# standalone-wifi-module-v1.net
KiCad netlist of a schematic drawn in EAGLE
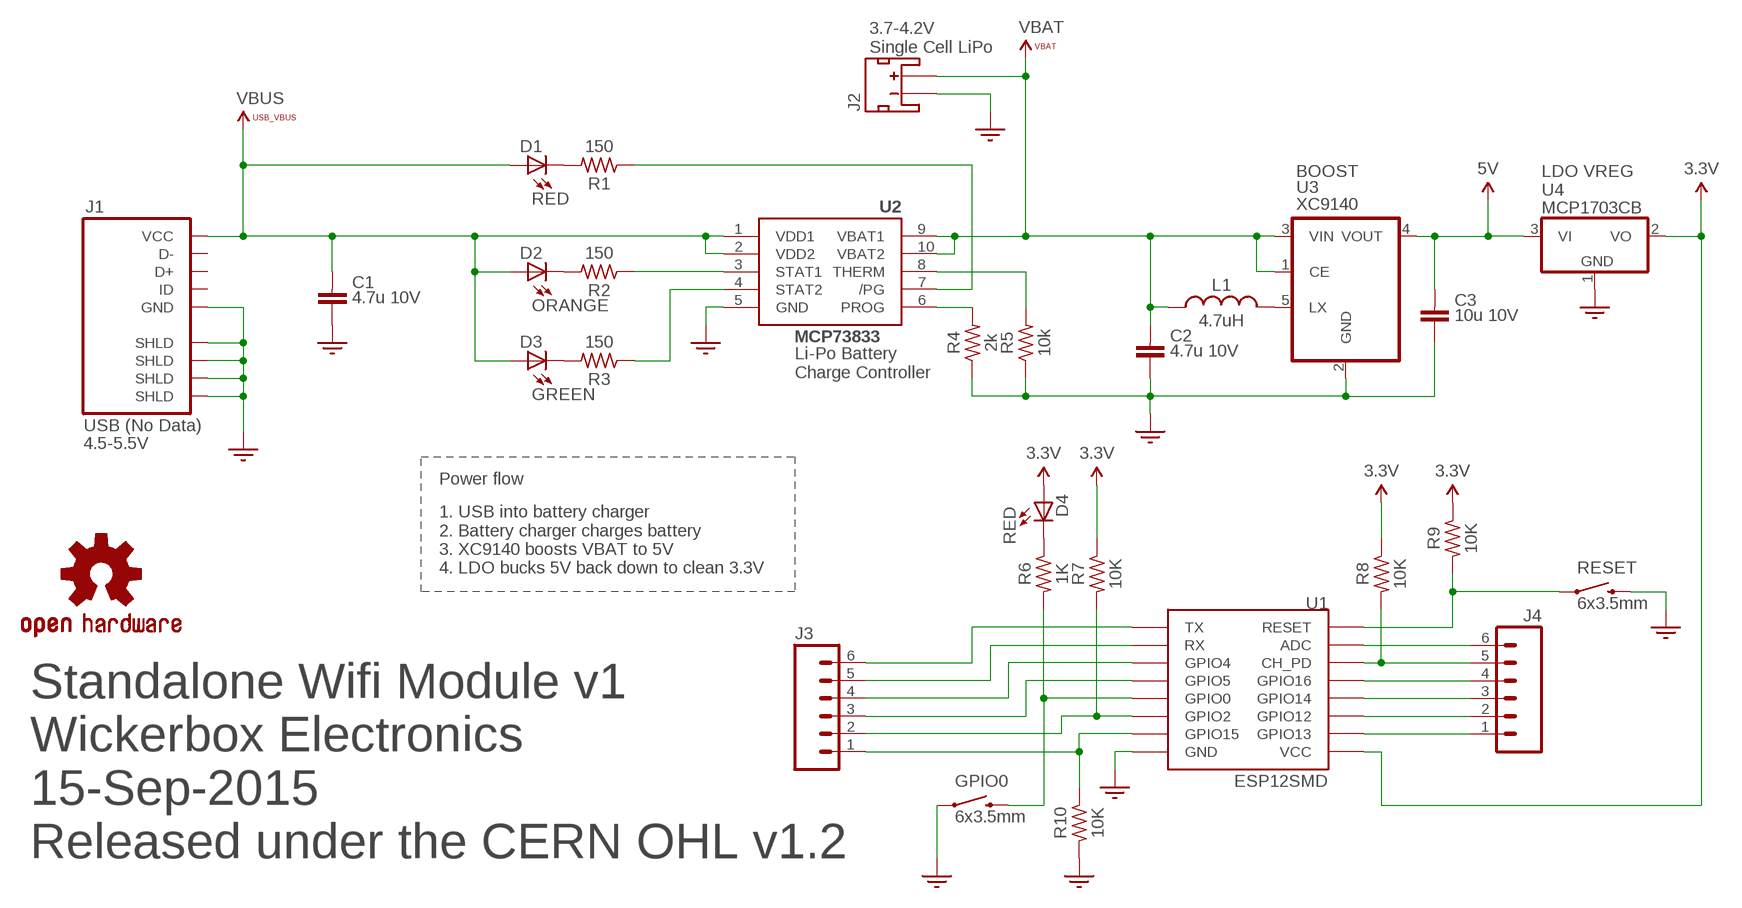
[diagram p0: schematic, sheet 1]

(export (version "E")
  (design (tool "Eeschema 10.0.6"))
  (components
    (comp (ref "C1")
      (value "4.7u 10V")
      (footprint "eagle-import:RLC-0805")
      (libsource (lib "eagle-import") (part "CAP-0805"))
    )
    (comp (ref "C2")
      (value "4.7u 10V")
      (footprint "eagle-import:RLC-0603")
      (libsource (lib "eagle-import") (part "CAP-0603"))
    )
    (comp (ref "C3")
      (value "10u 10V")
      (footprint "eagle-import:RLC-0603")
      (libsource (lib "eagle-import") (part "CAP-0603"))
    )
    (comp (ref "D1")
      (value "RED")
      (footprint "eagle-import:LED0603")
      (libsource (lib "eagle-import") (part "BG1111C"))
    )
    (comp (ref "D2")
      (value "ORANGE")
      (footprint "eagle-import:LED0603")
      (libsource (lib "eagle-import") (part "BG1111C"))
    )
    (comp (ref "D3")
      (value "GREEN")
      (footprint "eagle-import:LED0603")
      (libsource (lib "eagle-import") (part "BG1111C"))
    )
    (comp (ref "D4")
      (value "RED")
      (footprint "eagle-import:LED0603")
      (libsource (lib "eagle-import") (part "BG1111C"))
    )
    (comp (ref "GPIO0")
      (value "6x3.5mm")
      (footprint "eagle-import:TACTILE-SWITCH-1101NE")
      (libsource (lib "eagle-import") (part "SWITCH-MOMENTARY-2SMD-1101NE"))
    )
    (comp (ref "J1")
      (value "USB (No Data)")
      (footprint "eagle-import:ZX62D-B-5P8")
      (libsource (lib "eagle-import") (part "ZX62D-B-5P8"))
    )
    (comp (ref "J2")
      (value "JST_2MM_MALE")
      (footprint "eagle-import:JST-2-SMD")
      (libsource (lib "eagle-import") (part "JST_2MM_MALE"))
    )
    (comp (ref "J3")
      (value "M06LOCK_LONGPADS")
      (footprint "eagle-import:1X06_LOCK_LONGPADS")
      (libsource (lib "eagle-import") (part "M06LOCK_LONGPADS"))
    )
    (comp (ref "J4")
      (value "M06LOCK_LONGPADS")
      (footprint "eagle-import:1X06_LOCK_LONGPADS")
      (libsource (lib "eagle-import") (part "M06LOCK_LONGPADS"))
    )
    (comp (ref "L1")
      (value "4.7uH")
      (footprint "eagle-import:RLC-0805")
      (libsource (lib "eagle-import") (part "IND-0805"))
    )
    (comp (ref "R1")
      (value "150")
      (footprint "eagle-import:RLC-0402")
      (libsource (lib "eagle-import") (part "RES-0402"))
    )
    (comp (ref "R2")
      (value "150")
      (footprint "eagle-import:RLC-0402")
      (libsource (lib "eagle-import") (part "RES-0402"))
    )
    (comp (ref "R3")
      (value "150")
      (footprint "eagle-import:RLC-0402")
      (libsource (lib "eagle-import") (part "RES-0402"))
    )
    (comp (ref "R4")
      (value "2k")
      (footprint "eagle-import:RLC-0402")
      (libsource (lib "eagle-import") (part "RES-0402"))
    )
    (comp (ref "R5")
      (value "10k")
      (footprint "eagle-import:RLC-0402")
      (libsource (lib "eagle-import") (part "RES-0402"))
    )
    (comp (ref "R6")
      (value "1K")
      (footprint "eagle-import:RLC-0402")
      (libsource (lib "eagle-import") (part "RES-0402"))
    )
    (comp (ref "R7")
      (value "10K")
      (footprint "eagle-import:RLC-0402")
      (libsource (lib "eagle-import") (part "RES-0402"))
    )
    (comp (ref "R8")
      (value "10K")
      (footprint "eagle-import:RLC-0402")
      (libsource (lib "eagle-import") (part "RES-0402"))
    )
    (comp (ref "R9")
      (value "10K")
      (footprint "eagle-import:RLC-0402")
      (libsource (lib "eagle-import") (part "RES-0402"))
    )
    (comp (ref "R10")
      (value "10K")
      (footprint "eagle-import:RLC-0402")
      (libsource (lib "eagle-import") (part "RES-0402"))
    )
    (comp (ref "RESET")
      (value "6x3.5mm")
      (footprint "eagle-import:TACTILE-SWITCH-1101NE")
      (libsource (lib "eagle-import") (part "SWITCH-MOMENTARY-2SMD-1101NE"))
    )
    (comp (ref "U$2")
      (value "OSHW_LOGO_SYMM")
      (footprint "eagle-import:OSHW_LOGO_MED_SYM")
      (libsource (lib "eagle-import") (part "OSHW_LOGO_SYMM"))
    )
    (comp (ref "U1")
      (value "ESP12SMD")
      (footprint "eagle-import:ESP12_SMD")
      (libsource (lib "eagle-import") (part "ESP12SMD"))
    )
    (comp (ref "U2")
      (value "MCP73833-UN")
      (footprint "eagle-import:MSOP10")
      (libsource (lib "eagle-import") (part "MCP73833-UN"))
    )
    (comp (ref "U3")
      (value "XC9140")
      (footprint "eagle-import:SOT-25")
      (libsource (lib "eagle-import") (part "XC9140"))
    )
    (comp (ref "U4")
      (value "MCP1703CB")
      (footprint "eagle-import:SOT23")
      (libsource (lib "eagle-import") (part "MCP1703CB"))
    )
  )
  (nets
    (net (code "1") (name "3.3V") (class "Default")
      (node (ref "D4") (pin "A") (pinfunction "A_A") (pintype "passive"))
      (node (ref "R7") (pin "1") (pinfunction "1_1") (pintype "passive"))
      (node (ref "R8") (pin "1") (pinfunction "1_1") (pintype "passive"))
      (node (ref "R9") (pin "1") (pinfunction "1_1") (pintype "passive"))
      (node (ref "U1") (pin "VCC") (pinfunction "VCC_VCC") (pintype "bidirectional"))
      (node (ref "U4") (pin "2") (pinfunction "VO_2") (pintype "passive"))
    )
    (net (code "2") (name "5V") (class "Default")
      (node (ref "C3") (pin "2") (pinfunction "1_2") (pintype "passive"))
      (node (ref "U3") (pin "4") (pinfunction "VOUT_4") (pintype "bidirectional"))
      (node (ref "U4") (pin "3") (pinfunction "VI_3") (pintype "input"))
    )
    (net (code "3") (name "GND") (class "Default")
      (node (ref "C1") (pin "2") (pinfunction "2_2") (pintype "passive"))
      (node (ref "C2") (pin "1") (pinfunction "2_1") (pintype "passive"))
      (node (ref "C3") (pin "1") (pinfunction "2_1") (pintype "passive"))
      (node (ref "GPIO0") (pin "1") (pinfunction "1_1") (pintype "passive"))
      (node (ref "J1") (pin "P$1") (pinfunction "SHLD_P$1") (pintype "power_in"))
      (node (ref "J1") (pin "P$2") (pinfunction "SHLD_P$2") (pintype "power_in"))
      (node (ref "J1") (pin "P$3") (pinfunction "SHLD_P$3") (pintype "power_in"))
      (node (ref "J1") (pin "P$4") (pinfunction "SHLD_P$4") (pintype "power_in"))
      (node (ref "J1") (pin "P5") (pinfunction "GND_P5") (pintype "power_in"))
      (node (ref "J2") (pin "1") (pinfunction "-_1") (pintype "bidirectional"))
      (node (ref "R10") (pin "2") (pinfunction "2_2") (pintype "passive"))
      (node (ref "R4") (pin "1") (pinfunction "1_1") (pintype "passive"))
      (node (ref "R5") (pin "1") (pinfunction "1_1") (pintype "passive"))
      (node (ref "RESET") (pin "2") (pinfunction "2_2") (pintype "passive"))
      (node (ref "U1") (pin "GND") (pinfunction "GND_GND") (pintype "bidirectional"))
      (node (ref "U2") (pin "5") (pinfunction "GND_5") (pintype "power_in"))
      (node (ref "U3") (pin "2") (pinfunction "GND_2") (pintype "bidirectional"))
      (node (ref "U4") (pin "1") (pinfunction "GND_1") (pintype "passive"))
    )
    (net (code "4") (name "Net-(D1-PadC)") (class "Default")
      (node (ref "D1") (pin "C") (pinfunction "C_C") (pintype "passive"))
      (node (ref "R1") (pin "2") (pinfunction "2_2") (pintype "passive"))
    )
    (net (code "5") (name "Net-(D2-PadC)") (class "Default")
      (node (ref "D2") (pin "C") (pinfunction "C_C") (pintype "passive"))
      (node (ref "R2") (pin "2") (pinfunction "2_2") (pintype "passive"))
    )
    (net (code "6") (name "Net-(D3-PadC)") (class "Default")
      (node (ref "D3") (pin "C") (pinfunction "C_C") (pintype "passive"))
      (node (ref "R3") (pin "2") (pinfunction "2_2") (pintype "passive"))
    )
    (net (code "7") (name "Net-(D4-PadC)") (class "Default")
      (node (ref "D4") (pin "C") (pinfunction "C_C") (pintype "passive"))
      (node (ref "R6") (pin "1") (pinfunction "1_1") (pintype "passive"))
    )
    (net (code "8") (name "Net-(GPIO0-Pad2)") (class "Default")
      (node (ref "GPIO0") (pin "2") (pinfunction "2_2") (pintype "passive"))
      (node (ref "R6") (pin "2") (pinfunction "2_2") (pintype "passive"))
      (node (ref "U1") (pin "GPIO0") (pinfunction "GPIO0_GPIO0") (pintype "bidirectional"))
    )
    (net (code "9") (name "Net-(J3-Pad1)") (class "Default")
      (node (ref "J3") (pin "1") (pinfunction "1_1") (pintype "passive"))
      (node (ref "R10") (pin "1") (pinfunction "1_1") (pintype "passive"))
      (node (ref "U1") (pin "GPIO15") (pinfunction "GPIO15_GPIO15") (pintype "bidirectional"))
    )
    (net (code "10") (name "Net-(J3-Pad2)") (class "Default")
      (node (ref "J3") (pin "2") (pinfunction "2_2") (pintype "passive"))
      (node (ref "R7") (pin "2") (pinfunction "2_2") (pintype "passive"))
      (node (ref "U1") (pin "GPIO2") (pinfunction "GPIO2_GPIO2") (pintype "bidirectional"))
    )
    (net (code "11") (name "Net-(J3-Pad3)") (class "Default")
      (node (ref "J3") (pin "3") (pinfunction "3_3") (pintype "passive"))
      (node (ref "U1") (pin "GPIO5") (pinfunction "GPIO5_GPIO5") (pintype "bidirectional"))
    )
    (net (code "12") (name "Net-(J3-Pad4)") (class "Default")
      (node (ref "J3") (pin "4") (pinfunction "4_4") (pintype "passive"))
      (node (ref "U1") (pin "GPIO4") (pinfunction "GPIO4_GPIO4") (pintype "bidirectional"))
    )
    (net (code "13") (name "Net-(J3-Pad5)") (class "Default")
      (node (ref "J3") (pin "5") (pinfunction "5_5") (pintype "passive"))
      (node (ref "U1") (pin "RX") (pinfunction "RX_RX") (pintype "bidirectional"))
    )
    (net (code "14") (name "Net-(J3-Pad6)") (class "Default")
      (node (ref "J3") (pin "6") (pinfunction "6_6") (pintype "passive"))
      (node (ref "U1") (pin "TX") (pinfunction "TX_TX") (pintype "bidirectional"))
    )
    (net (code "15") (name "Net-(J4-Pad1)") (class "Default")
      (node (ref "J4") (pin "1") (pinfunction "1_1") (pintype "passive"))
      (node (ref "U1") (pin "GPIO13") (pinfunction "GPIO13_GPIO13") (pintype "bidirectional"))
    )
    (net (code "16") (name "Net-(J4-Pad2)") (class "Default")
      (node (ref "J4") (pin "2") (pinfunction "2_2") (pintype "passive"))
      (node (ref "U1") (pin "GPIO12") (pinfunction "GPIO12_GPIO12") (pintype "bidirectional"))
    )
    (net (code "17") (name "Net-(J4-Pad3)") (class "Default")
      (node (ref "J4") (pin "3") (pinfunction "3_3") (pintype "passive"))
      (node (ref "U1") (pin "GPIO14") (pinfunction "GPIO14_GPIO14") (pintype "bidirectional"))
    )
    (net (code "18") (name "Net-(J4-Pad4)") (class "Default")
      (node (ref "J4") (pin "4") (pinfunction "4_4") (pintype "passive"))
      (node (ref "U1") (pin "GPIO16") (pinfunction "GPIO16_GPIO16") (pintype "bidirectional"))
    )
    (net (code "19") (name "Net-(J4-Pad5)") (class "Default")
      (node (ref "J4") (pin "5") (pinfunction "5_5") (pintype "passive"))
      (node (ref "R8") (pin "2") (pinfunction "2_2") (pintype "passive"))
      (node (ref "U1") (pin "CH_PD") (pinfunction "CH_PD_CH_PD") (pintype "bidirectional"))
    )
    (net (code "20") (name "Net-(J4-Pad6)") (class "Default")
      (node (ref "J4") (pin "6") (pinfunction "6_6") (pintype "passive"))
      (node (ref "U1") (pin "ADC") (pinfunction "ADC_ADC") (pintype "bidirectional"))
    )
    (net (code "21") (name "Net-(R9-Pad2)") (class "Default")
      (node (ref "R9") (pin "2") (pinfunction "2_2") (pintype "passive"))
      (node (ref "RESET") (pin "1") (pinfunction "1_1") (pintype "passive"))
      (node (ref "U1") (pin "RESET") (pinfunction "RESET_RESET") (pintype "bidirectional"))
    )
    (net (code "22") (name "Net-(U2-PROG)") (class "Default")
      (node (ref "R4") (pin "2") (pinfunction "2_2") (pintype "passive"))
      (node (ref "U2") (pin "6") (pinfunction "PROG_6") (pintype "input"))
    )
    (net (code "23") (name "Net-(U2-STAT1)") (class "Default")
      (node (ref "R2") (pin "1") (pinfunction "1_1") (pintype "passive"))
      (node (ref "U2") (pin "3") (pinfunction "STAT1_3") (pintype "passive"))
    )
    (net (code "24") (name "Net-(U2-STAT2)") (class "Default")
      (node (ref "R3") (pin "1") (pinfunction "1_1") (pintype "passive"))
      (node (ref "U2") (pin "4") (pinfunction "STAT2_4") (pintype "passive"))
    )
    (net (code "25") (name "Net-(U2-THERM)") (class "Default")
      (node (ref "R5") (pin "2") (pinfunction "2_2") (pintype "passive"))
      (node (ref "U2") (pin "8") (pinfunction "THERM_8") (pintype "bidirectional"))
    )
    (net (code "26") (name "Net-(U2-{slash}PG)") (class "Default")
      (node (ref "R1") (pin "1") (pinfunction "1_1") (pintype "passive"))
      (node (ref "U2") (pin "7") (pinfunction "/PG_7") (pintype "passive"))
    )
    (net (code "27") (name "Net-(U3-LX)") (class "Default")
      (node (ref "L1") (pin "2") (pinfunction "2_2") (pintype "passive"))
      (node (ref "U3") (pin "5") (pinfunction "LX_5") (pintype "bidirectional"))
    )
    (net (code "28") (name "VBAT") (class "Default")
      (node (ref "C2") (pin "2") (pinfunction "1_2") (pintype "passive"))
      (node (ref "J2") (pin "2") (pinfunction "+_2") (pintype "bidirectional"))
      (node (ref "L1") (pin "1") (pinfunction "1_1") (pintype "passive"))
      (node (ref "U2") (pin "10") (pinfunction "VBAT2_10") (pintype "output"))
      (node (ref "U2") (pin "9") (pinfunction "VBAT1_9") (pintype "output"))
      (node (ref "U3") (pin "1") (pinfunction "CE_1") (pintype "bidirectional"))
      (node (ref "U3") (pin "3") (pinfunction "VIN_3") (pintype "bidirectional"))
    )
    (net (code "29") (name "VBUS") (class "Default")
      (node (ref "C1") (pin "1") (pinfunction "1_1") (pintype "passive"))
      (node (ref "D1") (pin "A") (pinfunction "A_A") (pintype "passive"))
      (node (ref "D2") (pin "A") (pinfunction "A_A") (pintype "passive"))
      (node (ref "D3") (pin "A") (pinfunction "A_A") (pintype "passive"))
      (node (ref "J1") (pin "P1") (pinfunction "VCC_P1") (pintype "power_in"))
      (node (ref "U2") (pin "1") (pinfunction "VDD1_1") (pintype "power_in"))
      (node (ref "U2") (pin "2") (pinfunction "VDD2_2") (pintype "power_in"))
    )
    (net (code "30") (name "unconnected-(J1-D+-PadP3)") (class "Default")
      (node (ref "J1") (pin "P3") (pinfunction "D+_P3") (pintype "bidirectional"))
    )
    (net (code "31") (name "unconnected-(J1-D--PadP2)") (class "Default")
      (node (ref "J1") (pin "P2") (pinfunction "D-_P2") (pintype "bidirectional"))
    )
    (net (code "32") (name "unconnected-(J1-ID-PadP4)") (class "Default")
      (node (ref "J1") (pin "P4") (pinfunction "ID_P4") (pintype "bidirectional"))
    )
    (net (code "33") (name "unconnected-(J2-PAD1-PadNC1)") (class "Default")
      (node (ref "J2") (pin "NC1") (pinfunction "PAD1_NC1") (pintype "bidirectional"))
    )
    (net (code "34") (name "unconnected-(J2-PAD2-PadNC2)") (class "Default")
      (node (ref "J2") (pin "NC2") (pinfunction "PAD2_NC2") (pintype "bidirectional"))
    )
  )
)
